# Rev_1_0.net
KiCad netlist of a schematic drawn in Altium Designer
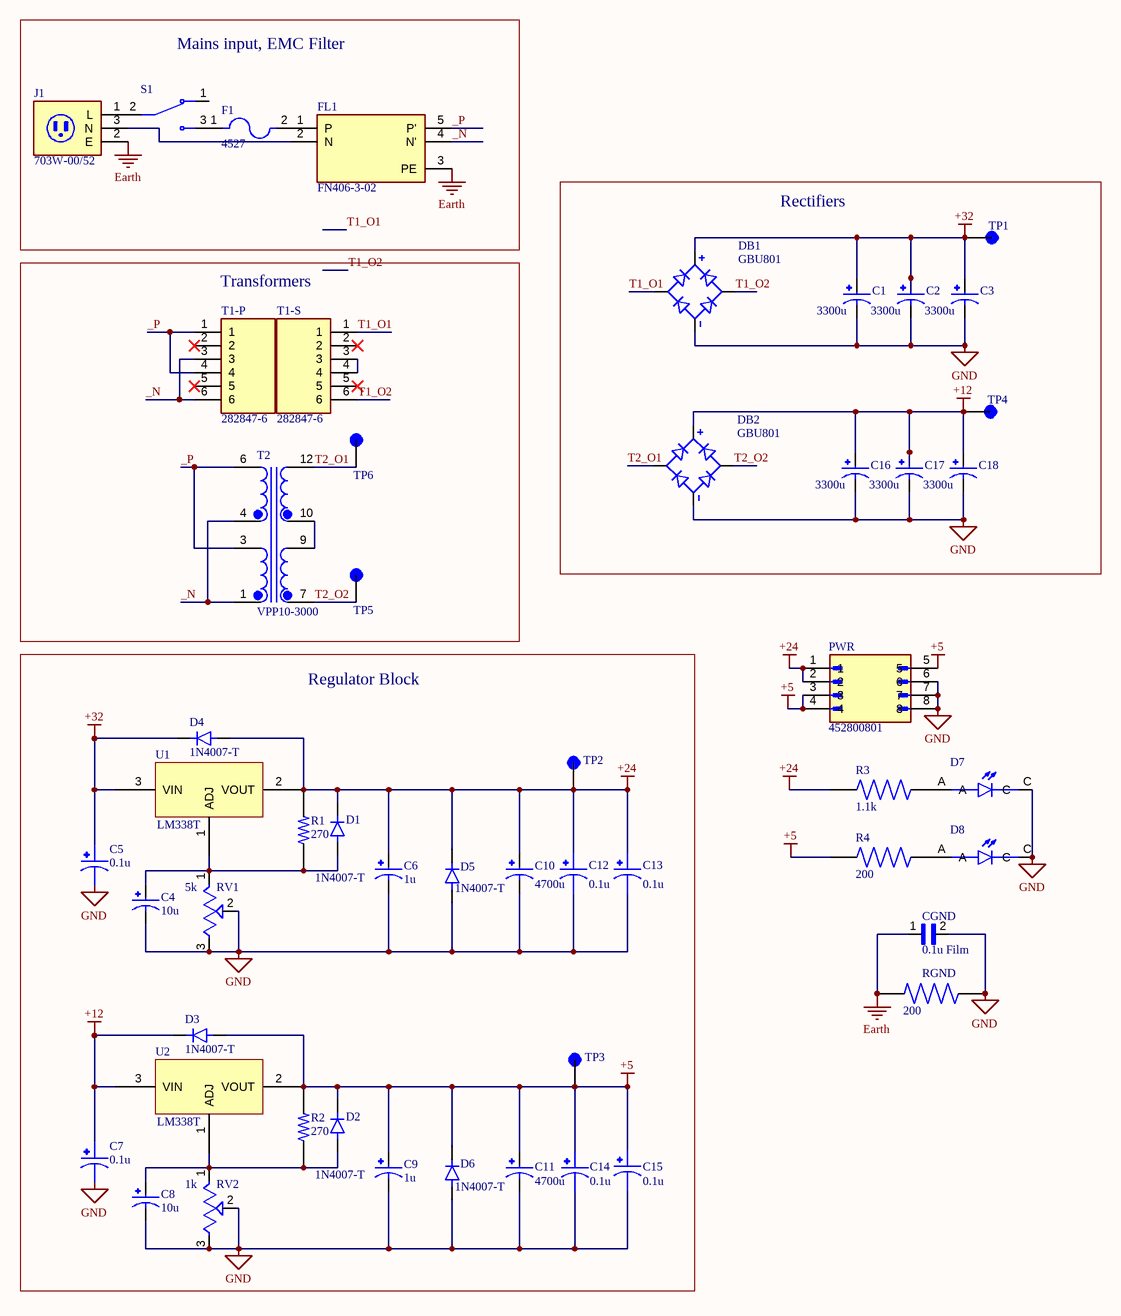
[diagram p0: Rev 1.0.SchDoc]

(export (version "E")
  (design (tool "Eeschema 10.0.6"))
  (components
    (comp (ref "C1")
      (value "UVZ1H332MHD")
      (footprint "CAPPRD750W80D1800H3550")
      (description "NHG-A")
      (fields (field (name "MP") "ECA1VHG472") (field (name "MF") "{'manufacturer': u'Panasonic'}"))
      (libsource (lib "Stepper_PSU") (part "ECA1VHG472"))
    )
    (comp (ref "C2")
      (value "UVZ1H332MHD")
      (footprint "CAPPRD750W80D1800H3550")
      (description "NHG-A")
      (fields (field (name "MP") "ECA1VHG472") (field (name "MF") "{'manufacturer': u'Panasonic'}"))
      (libsource (lib "Stepper_PSU") (part "ECA1VHG472"))
    )
    (comp (ref "C3")
      (value "UVZ1H332MHD")
      (footprint "CAPPRD750W80D1800H3550")
      (description "NHG-A")
      (fields (field (name "MP") "ECA1VHG472") (field (name "MF") "{'manufacturer': u'Panasonic'}"))
      (libsource (lib "Stepper_PSU") (part "ECA1VHG472"))
    )
    (comp (ref "C4")
      (value "10u")
      (footprint "6.35mm Tantalum Radial")
      (description "NHG-A")
      (fields (field (name "MP") "ECA1VHG472") (field (name "MF") "{'manufacturer': u'Panasonic'}"))
      (libsource (lib "Stepper_PSU") (part "ECA1VHG472"))
    )
    (comp (ref "C5")
      (value "0.1u")
      (footprint "CAPPRD200W50D550H1250")
      (description "0.47ÂµF 100V Aluminum Electrolytic Capacitors Radial, Can 2000 Hrs @ 85Â°C")
      (fields (field (name "MP") "UVR1H0R1MDD") (field (name "MF") "{'manufacturer': u'Nichicon'}"))
      (libsource (lib "Stepper_PSU") (part "UVR1H0R1MDD"))
    )
    (comp (ref "C6")
      (value "1u")
      (footprint "6.35mm Tantalum Radial")
      (description "NHG-A")
      (fields (field (name "MP") "ECA1VHG472") (field (name "MF") "{'manufacturer': u'Panasonic'}"))
      (libsource (lib "Stepper_PSU") (part "ECA1VHG472"))
    )
    (comp (ref "C7")
      (value "0.1u")
      (footprint "CAPPRD200W50D550H1250")
      (description "0.47ÂµF 100V Aluminum Electrolytic Capacitors Radial, Can 2000 Hrs @ 85Â°C")
      (fields (field (name "MP") "UVR1H0R1MDD") (field (name "MF") "{'manufacturer': u'Nichicon'}"))
      (libsource (lib "Stepper_PSU") (part "UVR1H0R1MDD"))
    )
    (comp (ref "C8")
      (value "10u")
      (footprint "6.35mm Tantalum Radial")
      (description "NHG-A")
      (fields (field (name "MP") "ECA1VHG472") (field (name "MF") "{'manufacturer': u'Panasonic'}"))
      (libsource (lib "Stepper_PSU") (part "ECA1VHG472"))
    )
    (comp (ref "C9")
      (value "1u")
      (footprint "6.35mm Tantalum Radial")
      (description "NHG-A")
      (fields (field (name "MP") "ECA1VHG472") (field (name "MF") "{'manufacturer': u'Panasonic'}"))
      (libsource (lib "Stepper_PSU") (part "ECA1VHG472"))
    )
    (comp (ref "C10")
      (value "4700u")
      (footprint "CAPPRD750W80D1800H3550")
      (description "NHG-A")
      (fields (field (name "MP") "ECA1VHG472") (field (name "MF") "{'manufacturer': u'Panasonic'}"))
      (libsource (lib "Stepper_PSU") (part "ECA1VHG472"))
    )
    (comp (ref "C11")
      (value "4700u")
      (footprint "CAPPRD750W80D1800H3550")
      (description "NHG-A")
      (fields (field (name "MP") "ECA1VHG472") (field (name "MF") "{'manufacturer': u'Panasonic'}"))
      (libsource (lib "Stepper_PSU") (part "ECA1VHG472"))
    )
    (comp (ref "C12")
      (value "0.1u")
      (footprint "CAPPRD200W50D550H1250")
      (description "0.47ÂµF 100V Aluminum Electrolytic Capacitors Radial, Can 2000 Hrs @ 85Â°C")
      (fields (field (name "MP") "UVR1H0R1MDD") (field (name "MF") "{'manufacturer': u'Nichicon'}"))
      (libsource (lib "Stepper_PSU") (part "UVR1H0R1MDD"))
    )
    (comp (ref "C13")
      (value "0.1u")
      (footprint "CAPPRD200W50D550H1250")
      (description "0.47ÂµF 100V Aluminum Electrolytic Capacitors Radial, Can 2000 Hrs @ 85Â°C")
      (fields (field (name "MP") "UVR1H0R1MDD") (field (name "MF") "{'manufacturer': u'Nichicon'}"))
      (libsource (lib "Stepper_PSU") (part "UVR1H0R1MDD"))
    )
    (comp (ref "C14")
      (value "0.1u")
      (footprint "CAPPRD200W50D550H1250")
      (description "0.47ÂµF 100V Aluminum Electrolytic Capacitors Radial, Can 2000 Hrs @ 85Â°C")
      (fields (field (name "MP") "UVR1H0R1MDD") (field (name "MF") "{'manufacturer': u'Nichicon'}"))
      (libsource (lib "Stepper_PSU") (part "UVR1H0R1MDD"))
    )
    (comp (ref "C15")
      (value "0.1u")
      (footprint "CAPPRD200W50D550H1250")
      (description "0.47ÂµF 100V Aluminum Electrolytic Capacitors Radial, Can 2000 Hrs @ 85Â°C")
      (fields (field (name "MP") "UVR1H0R1MDD") (field (name "MF") "{'manufacturer': u'Nichicon'}"))
      (libsource (lib "Stepper_PSU") (part "UVR1H0R1MDD"))
    )
    (comp (ref "C16")
      (value "UVZ1H332MHD")
      (footprint "CAPPRD750W80D1800H3550")
      (description "NHG-A")
      (fields (field (name "MP") "ECA1VHG472") (field (name "MF") "{'manufacturer': u'Panasonic'}"))
      (libsource (lib "Stepper_PSU") (part "ECA1VHG472"))
    )
    (comp (ref "C17")
      (value "UVZ1H332MHD")
      (footprint "CAPPRD750W80D1800H3550")
      (description "NHG-A")
      (fields (field (name "MP") "ECA1VHG472") (field (name "MF") "{'manufacturer': u'Panasonic'}"))
      (libsource (lib "Stepper_PSU") (part "ECA1VHG472"))
    )
    (comp (ref "C18")
      (value "UVZ1H332MHD")
      (footprint "CAPPRD750W80D1800H3550")
      (description "NHG-A")
      (fields (field (name "MP") "ECA1VHG472") (field (name "MF") "{'manufacturer': u'Panasonic'}"))
      (libsource (lib "Stepper_PSU") (part "ECA1VHG472"))
    )
    (comp (ref "CGND")
      (value "0.1u Film")
      (footprint "CAPRR500W50L730T450H950")
      (fields (field (name "MP") "B32529C3104K289") (field (name "MF") "{'manufacturer': u'EPCOS'}"))
      (libsource (lib "Stepper_PSU") (part "B32529C3104K289"))
    )
    (comp (ref "D1")
      (value "1N4007-T")
      (footprint "DIOAD780W78L463D236")
      (fields (field (name "MF") "{'manufacturer': u'Diodes Incorporated'}"))
      (libsource (lib "Stepper_PSU") (part "1N4007-T"))
    )
    (comp (ref "D2")
      (value "1N4007-T")
      (footprint "DIOAD780W78L463D236")
      (fields (field (name "MF") "{'manufacturer': u'Diodes Incorporated'}"))
      (libsource (lib "Stepper_PSU") (part "1N4007-T"))
    )
    (comp (ref "D3")
      (value "1N4007-T")
      (footprint "DIOAD780W78L463D236")
      (fields (field (name "MF") "{'manufacturer': u'Diodes Incorporated'}"))
      (libsource (lib "Stepper_PSU") (part "1N4007-T"))
    )
    (comp (ref "D4")
      (value "1N4007-T")
      (footprint "DIOAD780W78L463D236")
      (fields (field (name "MF") "{'manufacturer': u'Diodes Incorporated'}"))
      (libsource (lib "Stepper_PSU") (part "1N4007-T"))
    )
    (comp (ref "D5")
      (value "1N4007-T")
      (footprint "DIOAD780W78L463D236")
      (fields (field (name "MF") "{'manufacturer': u'Diodes Incorporated'}"))
      (libsource (lib "Stepper_PSU") (part "1N4007-T"))
    )
    (comp (ref "D6")
      (value "1N4007-T")
      (footprint "DIOAD780W78L463D236")
      (fields (field (name "MF") "{'manufacturer': u'Diodes Incorporated'}"))
      (libsource (lib "Stepper_PSU") (part "1N4007-T"))
    )
    (comp (ref "D7")
      (value "WP7113ID")
      (footprint "WP7113ID:LED_WP7113ID")
      (description "LED; Thru-Hole; Green; T1-3/4; 5mm; Clear Lens; 25ma; 565nm; 200mcd; Round")
      (fields (field (name "MF") "{'manufacturer': u'Kingbright'}"))
      (libsource (lib "*") (part "WP7113ID"))
    )
    (comp (ref "D8")
      (value "WP7113ID")
      (footprint "WP7113ID:LED_WP7113ID")
      (description "LED; Thru-Hole; Green; T1-3/4; 5mm; Clear Lens; 25ma; 565nm; 200mcd; Round")
      (fields (field (name "MF") "{'manufacturer': u'Kingbright'}"))
      (libsource (lib "*") (part "WP7113ID"))
    )
    (comp (ref "DB1")
      (value "GBU801")
      (footprint "SIP343W114P508L2205H2134Q4")
      (fields (field (name "MF") "{'manufacturer': u'Diodes Inc.'}"))
      (libsource (lib "Stepper_PSU") (part "GBU801"))
    )
    (comp (ref "DB2")
      (value "GBU801")
      (footprint "SIP343W114P508L2205H2134Q4")
      (fields (field (name "MF") "{'manufacturer': u'Diodes Inc.'}"))
      (libsource (lib "Stepper_PSU") (part "GBU801"))
    )
    (comp (ref "F1")
      (value "4527")
      (footprint "FUSE_4527")
      (fields (field (name "MF") "{'manufacturer': u'Keystone'}"))
      (libsource (lib "Stepper_PSU") (part "4527"))
    )
    (comp (ref "FL1")
      (value "FN406-3-02")
      (footprint "FIL_FN406-3-02")
      (description "Single Phase EMC/EMI Line Filter 3A 250VAC DC ~ 400Hz Single Stage PC Pins")
      (fields (field (name "MF") "{'manufacturer': u'Schaffner EMC'}"))
      (libsource (lib "Stepper_PSU") (part "FN406-3-02"))
    )
    (comp (ref "J1")
      (value "703W-00/52")
      (footprint "703W-00_52:QUALTEK_703W-00/52")
      (description "3 Position 250 V 10 A Male Pins AC Receptacle Right Angle Connector")
      (fields (field (name "MF") "{'manufacturer': u'Qualtek'}"))
      (libsource (lib "*") (part "703W-00/52"))
    )
    (comp (ref "PWR")
      (value "452800801")
      (footprint "MOLEX_452800801")
      (fields (field (name "MF") "{'manufacturer': u'Molex'}"))
      (libsource (lib "Stepper_Controller") (part "452800801"))
    )
    (comp (ref "R1")
      (value "270")
      (footprint "RESAD730W45L360D200")
      (description "Res Carbon Film 680 Ohm 5% 0.125W(1/8W) -400ppm/C to 0ppm/C Conformal Coated AXL T/R")
      (fields
        (field (name "MP") "CF18JT680R")
        (field (name "MF") "{'manufacturer': u'Stackpole Electronics'}")
      )
      (libsource (lib "Stepper_PSU") (part "CF18JT680R"))
    )
    (comp (ref "R2")
      (value "270")
      (footprint "RESAD730W45L360D200")
      (description "Res Carbon Film 680 Ohm 5% 0.125W(1/8W) -400ppm/C to 0ppm/C Conformal Coated AXL T/R")
      (fields
        (field (name "MP") "CF18JT680R")
        (field (name "MF") "{'manufacturer': u'Stackpole Electronics'}")
      )
      (libsource (lib "Stepper_PSU") (part "CF18JT680R"))
    )
    (comp (ref "R3")
      (value "1.1k")
      (footprint "RESAD1520W70L1030D380")
      (description "5.1 Ohms +/-5% 0.5W, 1/2W Through Hole Resistor Axial Pulse Withstanding Carbon Composition")
      (fields
        (field (name "MF") "{'manufacturer': u'TE Connectivity / AMP'}")
        (field (name "MP") "CBT50J5R1")
      )
      (libsource (lib "Stepper_PSU") (part "CBT50J5R1"))
    )
    (comp (ref "R4")
      (value "200")
      (footprint "RESAD1520W70L1030D380")
      (description "5.1 Ohms +/-5% 0.5W, 1/2W Through Hole Resistor Axial Pulse Withstanding Carbon Composition")
      (fields
        (field (name "MF") "{'manufacturer': u'TE Connectivity / AMP'}")
        (field (name "MP") "CBT50J5R1")
      )
      (libsource (lib "Stepper_PSU") (part "CBT50J5R1"))
    )
    (comp (ref "RGND")
      (value "200")
      (footprint "RESAD1520W70L1030D380")
      (description "5.1 Ohms +/-5% 0.5W, 1/2W Through Hole Resistor Axial Pulse Withstanding Carbon Composition")
      (fields
        (field (name "MF") "{'manufacturer': u'TE Connectivity / AMP'}")
        (field (name "MP") "CBT50J5R1")
      )
      (libsource (lib "Stepper_PSU") (part "CBT50J5R1"))
    )
    (comp (ref "RV1")
      (value "5k")
      (footprint "TRIM_3306F-1-502")
      (description "2 kOhms 0.2W, 1/5W PC Pins Through Hole Trimmer Potentiometer Cermet 1 Turn Top Adjustment")
      (fields (field (name "MP") "3306F-1-502") (field (name "MF") "{'manufacturer': u'Bourns'}"))
      (libsource (lib "Stepper_PSU") (part "3306F-1-502"))
    )
    (comp (ref "RV2")
      (value "1k")
      (footprint "TRIM_3306F-1-502")
      (description "2 kOhms 0.2W, 1/5W PC Pins Through Hole Trimmer Potentiometer Cermet 1 Turn Top Adjustment")
      (fields (field (name "MP") "3306F-1-502") (field (name "MF") "{'manufacturer': u'Bourns'}"))
      (libsource (lib "Stepper_PSU") (part "3306F-1-502"))
    )
    (comp (ref "S1")
      (value "300SP1J1BLKM7QE")
      (footprint "SW_300SP1J1BLKM7QE")
      (fields (field (name "MF") "{'manufacturer': u'E-Switch'}"))
      (libsource (lib "Stepper_PSU") (part "300SP1J1BLKM7QE"))
    )
    (comp (ref "T1-P")
      (value "282847-6")
      (footprint "TE_282847-6")
      (fields (field (name "MF") "{'manufacturer': u'TE Connectivity'}"))
      (libsource (lib "Stepper_PSU") (part "282847-6"))
    )
    (comp (ref "T1-S")
      (value "282847-6")
      (footprint "TE_282847-6")
      (fields (field (name "MF") "{'manufacturer': u'TE Connectivity'}"))
      (libsource (lib "") (part "282847-6_1"))
    )
    (comp (ref "T2")
      (value "VPP10-3000")
      (footprint "XFMR_VPP10-3000")
      (description "Power Transformer 4000Vrms Dual Prim. Dual Sec. 230V/115V Prim. 10V/5V Sec. Through Hole")
      (fields (field (name "MF") "{'manufacturer': u'Triad Magnetics'}"))
      (libsource (lib "Stepper_PSU") (part "VPP10-3000"))
    )
    (comp (ref "TP1")
      (value "5000")
      (footprint "KEYSTONE_5000")
      (fields (field (name "MF") "{'manufacturer': u'Keystone Electronics'}"))
      (libsource (lib "Stepper_PSU") (part "5000"))
    )
    (comp (ref "TP2")
      (value "5000")
      (footprint "KEYSTONE_5000")
      (fields (field (name "MF") "{'manufacturer': u'Keystone Electronics'}"))
      (libsource (lib "Stepper_PSU") (part "5000"))
    )
    (comp (ref "TP3")
      (value "5000")
      (footprint "KEYSTONE_5000")
      (fields (field (name "MF") "{'manufacturer': u'Keystone Electronics'}"))
      (libsource (lib "Stepper_PSU") (part "5000"))
    )
    (comp (ref "TP4")
      (value "5000")
      (footprint "KEYSTONE_5000")
      (fields (field (name "MF") "{'manufacturer': u'Keystone Electronics'}"))
      (libsource (lib "Stepper_PSU") (part "5000"))
    )
    (comp (ref "TP5")
      (value "5000")
      (footprint "KEYSTONE_5000")
      (fields (field (name "MF") "{'manufacturer': u'Keystone Electronics'}"))
      (libsource (lib "Stepper_PSU") (part "5000"))
    )
    (comp (ref "TP6")
      (value "5000")
      (footprint "KEYSTONE_5000")
      (fields (field (name "MF") "{'manufacturer': u'Keystone Electronics'}"))
      (libsource (lib "Stepper_PSU") (part "5000"))
    )
    (comp (ref "U1")
      (value "LM338T")
      (footprint "TO254P1054X470X1955-3")
      (libsource (lib "PSULib") (part "LM338T/NOPB-ND"))
    )
    (comp (ref "U2")
      (value "LM338T")
      (footprint "TO254P1054X470X1955-3")
      (libsource (lib "PSULib") (part "LM338T/NOPB-ND"))
    )
  )
  (nets
    (net (code "1") (name "+5") (class "Default")
      (node (ref "C11") (pin "P") (pinfunction "P_P") (pintype "passive"))
      (node (ref "C14") (pin "1") (pinfunction "1_1") (pintype "passive"))
      (node (ref "C15") (pin "1") (pinfunction "1_1") (pintype "passive"))
      (node (ref "C9") (pin "P") (pinfunction "P_P") (pintype "passive"))
      (node (ref "D2") (pin "K") (pinfunction "K_K") (pintype "passive"))
      (node (ref "D3") (pin "A") (pinfunction "A_A") (pintype "passive"))
      (node (ref "D6") (pin "K") (pinfunction "K_K") (pintype "passive"))
      (node (ref "PWR") (pin "3") (pinfunction "3_3") (pintype "passive"))
      (node (ref "PWR") (pin "4") (pinfunction "4_4") (pintype "passive"))
      (node (ref "PWR") (pin "5") (pinfunction "5_5") (pintype "passive"))
      (node (ref "R2") (pin "2") (pinfunction "2_2") (pintype "passive"))
      (node (ref "R4") (pin "1") (pinfunction "1_1") (pintype "passive"))
      (node (ref "TP3") (pin "TP") (pinfunction "TP_TP") (pintype "passive"))
      (node (ref "U2") (pin "2") (pinfunction "VOUT_2") (pintype "passive"))
    )
    (net (code "2") (name "+12") (class "Default")
      (node (ref "C16") (pin "P") (pinfunction "P_P") (pintype "passive"))
      (node (ref "C17") (pin "P") (pinfunction "P_P") (pintype "passive"))
      (node (ref "C18") (pin "P") (pinfunction "P_P") (pintype "passive"))
      (node (ref "C7") (pin "1") (pinfunction "1_1") (pintype "passive"))
      (node (ref "D3") (pin "K") (pinfunction "K_K") (pintype "passive"))
      (node (ref "DB2") (pin "POS") (pinfunction "POS_POS") (pintype "passive"))
      (node (ref "TP4") (pin "TP") (pinfunction "TP_TP") (pintype "passive"))
      (node (ref "U2") (pin "3") (pinfunction "VIN_3") (pintype "passive"))
    )
    (net (code "3") (name "+24") (class "Default")
      (node (ref "C10") (pin "P") (pinfunction "P_P") (pintype "passive"))
      (node (ref "C12") (pin "1") (pinfunction "1_1") (pintype "passive"))
      (node (ref "C13") (pin "1") (pinfunction "1_1") (pintype "passive"))
      (node (ref "C6") (pin "P") (pinfunction "P_P") (pintype "passive"))
      (node (ref "D1") (pin "K") (pinfunction "K_K") (pintype "passive"))
      (node (ref "D4") (pin "A") (pinfunction "A_A") (pintype "passive"))
      (node (ref "D5") (pin "K") (pinfunction "K_K") (pintype "passive"))
      (node (ref "PWR") (pin "1") (pinfunction "1_1") (pintype "passive"))
      (node (ref "PWR") (pin "2") (pinfunction "2_2") (pintype "passive"))
      (node (ref "R1") (pin "2") (pinfunction "2_2") (pintype "passive"))
      (node (ref "R3") (pin "1") (pinfunction "1_1") (pintype "passive"))
      (node (ref "TP2") (pin "TP") (pinfunction "TP_TP") (pintype "passive"))
      (node (ref "U1") (pin "2") (pinfunction "VOUT_2") (pintype "passive"))
    )
    (net (code "4") (name "+32") (class "Default")
      (node (ref "C1") (pin "P") (pinfunction "P_P") (pintype "passive"))
      (node (ref "C2") (pin "P") (pinfunction "P_P") (pintype "passive"))
      (node (ref "C3") (pin "P") (pinfunction "P_P") (pintype "passive"))
      (node (ref "C5") (pin "1") (pinfunction "1_1") (pintype "passive"))
      (node (ref "D4") (pin "K") (pinfunction "K_K") (pintype "passive"))
      (node (ref "DB1") (pin "POS") (pinfunction "POS_POS") (pintype "passive"))
      (node (ref "TP1") (pin "TP") (pinfunction "TP_TP") (pintype "passive"))
      (node (ref "U1") (pin "3") (pinfunction "VIN_3") (pintype "passive"))
    )
    (net (code "5") (name "/T1_O1") (class "Default")
      (node (ref "DB1") (pin "AC2") (pinfunction "AC2_AC2") (pintype "passive"))
      (node (ref "T1-S") (pin "1") (pinfunction "1_1") (pintype "passive"))
    )
    (net (code "6") (name "/T1_O2") (class "Default")
      (node (ref "DB1") (pin "AC1") (pinfunction "AC1_AC1") (pintype "passive"))
      (node (ref "T1-S") (pin "6") (pinfunction "6_6") (pintype "passive"))
    )
    (net (code "7") (name "/T2_O1") (class "Default")
      (node (ref "DB2") (pin "AC2") (pinfunction "AC2_AC2") (pintype "passive"))
      (node (ref "T2") (pin "12") (pinfunction "12_12") (pintype "passive"))
      (node (ref "TP6") (pin "TP") (pinfunction "TP_TP") (pintype "passive"))
    )
    (net (code "8") (name "/T2_O2") (class "Default")
      (node (ref "DB2") (pin "AC1") (pinfunction "AC1_AC1") (pintype "passive"))
      (node (ref "T2") (pin "7") (pinfunction "7_7") (pintype "passive"))
      (node (ref "TP5") (pin "TP") (pinfunction "TP_TP") (pintype "passive"))
    )
    (net (code "9") (name "/_N") (class "Default")
      (node (ref "FL1") (pin "4") (pinfunction "N'_4") (pintype "passive"))
      (node (ref "T1-P") (pin "3") (pinfunction "3_3") (pintype "passive"))
      (node (ref "T1-P") (pin "6") (pinfunction "6_6") (pintype "passive"))
      (node (ref "T2") (pin "1") (pinfunction "1_1") (pintype "passive"))
      (node (ref "T2") (pin "4") (pinfunction "4_4") (pintype "passive"))
    )
    (net (code "10") (name "/_P") (class "Default")
      (node (ref "FL1") (pin "5") (pinfunction "P'_5") (pintype "passive"))
      (node (ref "T1-P") (pin "1") (pinfunction "1_1") (pintype "passive"))
      (node (ref "T1-P") (pin "4") (pinfunction "4_4") (pintype "passive"))
      (node (ref "T2") (pin "3") (pinfunction "3_3") (pintype "passive"))
      (node (ref "T2") (pin "6") (pinfunction "6_6") (pintype "passive"))
    )
    (net (code "11") (name "Earth") (class "Default")
      (node (ref "CGND") (pin "1") (pinfunction "1_1") (pintype "passive"))
      (node (ref "FL1") (pin "3") (pinfunction "PE_3") (pintype "power_in"))
      (node (ref "J1") (pin "2") (pinfunction "E_2") (pintype "power_in"))
      (node (ref "RGND") (pin "1") (pinfunction "1_1") (pintype "passive"))
    )
    (net (code "12") (name "GND") (class "Default")
      (node (ref "C1") (pin "N") (pinfunction "N_N") (pintype "passive"))
      (node (ref "C10") (pin "N") (pinfunction "N_N") (pintype "passive"))
      (node (ref "C11") (pin "N") (pinfunction "N_N") (pintype "passive"))
      (node (ref "C12") (pin "2") (pinfunction "2_2") (pintype "passive"))
      (node (ref "C13") (pin "2") (pinfunction "2_2") (pintype "passive"))
      (node (ref "C14") (pin "2") (pinfunction "2_2") (pintype "passive"))
      (node (ref "C15") (pin "2") (pinfunction "2_2") (pintype "passive"))
      (node (ref "C16") (pin "N") (pinfunction "N_N") (pintype "passive"))
      (node (ref "C17") (pin "N") (pinfunction "N_N") (pintype "passive"))
      (node (ref "C18") (pin "N") (pinfunction "N_N") (pintype "passive"))
      (node (ref "C2") (pin "N") (pinfunction "N_N") (pintype "passive"))
      (node (ref "C3") (pin "N") (pinfunction "N_N") (pintype "passive"))
      (node (ref "C4") (pin "N") (pinfunction "N_N") (pintype "passive"))
      (node (ref "C5") (pin "2") (pinfunction "2_2") (pintype "passive"))
      (node (ref "C6") (pin "N") (pinfunction "N_N") (pintype "passive"))
      (node (ref "C7") (pin "2") (pinfunction "2_2") (pintype "passive"))
      (node (ref "C8") (pin "N") (pinfunction "N_N") (pintype "passive"))
      (node (ref "C9") (pin "N") (pinfunction "N_N") (pintype "passive"))
      (node (ref "CGND") (pin "2") (pinfunction "2_2") (pintype "passive"))
      (node (ref "D5") (pin "A") (pinfunction "A_A") (pintype "passive"))
      (node (ref "D6") (pin "A") (pinfunction "A_A") (pintype "passive"))
      (node (ref "D7") (pin "C") (pinfunction "C_C") (pintype "passive"))
      (node (ref "D8") (pin "C") (pinfunction "C_C") (pintype "passive"))
      (node (ref "DB1") (pin "NEG") (pinfunction "NEG_NEG") (pintype "passive"))
      (node (ref "DB2") (pin "NEG") (pinfunction "NEG_NEG") (pintype "passive"))
      (node (ref "PWR") (pin "6") (pinfunction "6_6") (pintype "passive"))
      (node (ref "PWR") (pin "7") (pinfunction "7_7") (pintype "passive"))
      (node (ref "PWR") (pin "8") (pinfunction "8_8") (pintype "passive"))
      (node (ref "RGND") (pin "2") (pinfunction "2_2") (pintype "passive"))
      (node (ref "RV1") (pin "2") (pinfunction "W_2") (pintype "passive"))
      (node (ref "RV1") (pin "3") (pinfunction "CW_3") (pintype "passive"))
      (node (ref "RV2") (pin "2") (pinfunction "W_2") (pintype "passive"))
      (node (ref "RV2") (pin "3") (pinfunction "CW_3") (pintype "passive"))
    )
    (net (code "13") (name "Net-(D7-PadA)") (class "Default")
      (node (ref "D7") (pin "A") (pinfunction "A_A") (pintype "passive"))
      (node (ref "R3") (pin "2") (pinfunction "2_2") (pintype "passive"))
    )
    (net (code "14") (name "Net-(D8-PadA)") (class "Default")
      (node (ref "D8") (pin "A") (pinfunction "A_A") (pintype "passive"))
      (node (ref "R4") (pin "2") (pinfunction "2_2") (pintype "passive"))
    )
    (net (code "15") (name "Net-(F1-Pad1)") (class "Default")
      (node (ref "F1") (pin "1") (pinfunction "1_1") (pintype "passive"))
      (node (ref "S1") (pin "3") (pinfunction "3_3") (pintype "passive"))
    )
    (net (code "16") (name "Net-(FL1-N)") (class "Default")
      (node (ref "FL1") (pin "2") (pinfunction "N_2") (pintype "passive"))
      (node (ref "J1") (pin "3") (pinfunction "N_3") (pintype "power_in"))
    )
    (net (code "17") (name "Net-(FL1-P)") (class "Default")
      (node (ref "F1") (pin "2") (pinfunction "2_2") (pintype "passive"))
      (node (ref "FL1") (pin "1") (pinfunction "P_1") (pintype "passive"))
    )
    (net (code "18") (name "Net-(J1-L)") (class "Default")
      (node (ref "J1") (pin "1") (pinfunction "L_1") (pintype "power_in"))
      (node (ref "S1") (pin "2") (pinfunction "2_2") (pintype "passive"))
    )
    (net (code "19") (name "Net-(RV1-CCW)") (class "Default")
      (node (ref "C4") (pin "P") (pinfunction "P_P") (pintype "passive"))
      (node (ref "D1") (pin "A") (pinfunction "A_A") (pintype "passive"))
      (node (ref "R1") (pin "1") (pinfunction "1_1") (pintype "passive"))
      (node (ref "RV1") (pin "1") (pinfunction "CCW_1") (pintype "passive"))
      (node (ref "U1") (pin "1") (pinfunction "ADJ_1") (pintype "passive"))
    )
    (net (code "20") (name "Net-(RV2-CCW)") (class "Default")
      (node (ref "C8") (pin "P") (pinfunction "P_P") (pintype "passive"))
      (node (ref "D2") (pin "A") (pinfunction "A_A") (pintype "passive"))
      (node (ref "R2") (pin "1") (pinfunction "1_1") (pintype "passive"))
      (node (ref "RV2") (pin "1") (pinfunction "CCW_1") (pintype "passive"))
      (node (ref "U2") (pin "1") (pinfunction "ADJ_1") (pintype "passive"))
    )
    (net (code "21") (name "Net-(T1-S-Pad3)") (class "Default")
      (node (ref "T1-S") (pin "3") (pinfunction "3_3") (pintype "passive"))
      (node (ref "T1-S") (pin "4") (pinfunction "4_4") (pintype "passive"))
    )
    (net (code "22") (name "Net-(T2-Pad10)") (class "Default")
      (node (ref "T2") (pin "10") (pinfunction "10_10") (pintype "passive"))
      (node (ref "T2") (pin "9") (pinfunction "9_9") (pintype "passive"))
    )
    (net (code "23") (name "unconnected-(S1-Pad1)") (class "Default")
      (node (ref "S1") (pin "1") (pinfunction "1_1") (pintype "passive"))
    )
    (net (code "24") (name "unconnected-(T1-P-Pad2)") (class "Default")
      (node (ref "T1-P") (pin "2") (pinfunction "2_2") (pintype "passive+no_connect"))
    )
    (net (code "25") (name "unconnected-(T1-P-Pad5)") (class "Default")
      (node (ref "T1-P") (pin "5") (pinfunction "5_5") (pintype "passive+no_connect"))
    )
    (net (code "26") (name "unconnected-(T1-S-Pad2)") (class "Default")
      (node (ref "T1-S") (pin "2") (pinfunction "2_2") (pintype "passive+no_connect"))
    )
    (net (code "27") (name "unconnected-(T1-S-Pad5)") (class "Default")
      (node (ref "T1-S") (pin "5") (pinfunction "5_5") (pintype "passive+no_connect"))
    )
  )
)
